# Codec_main.net
KiCad netlist of a schematic drawn in EAGLE
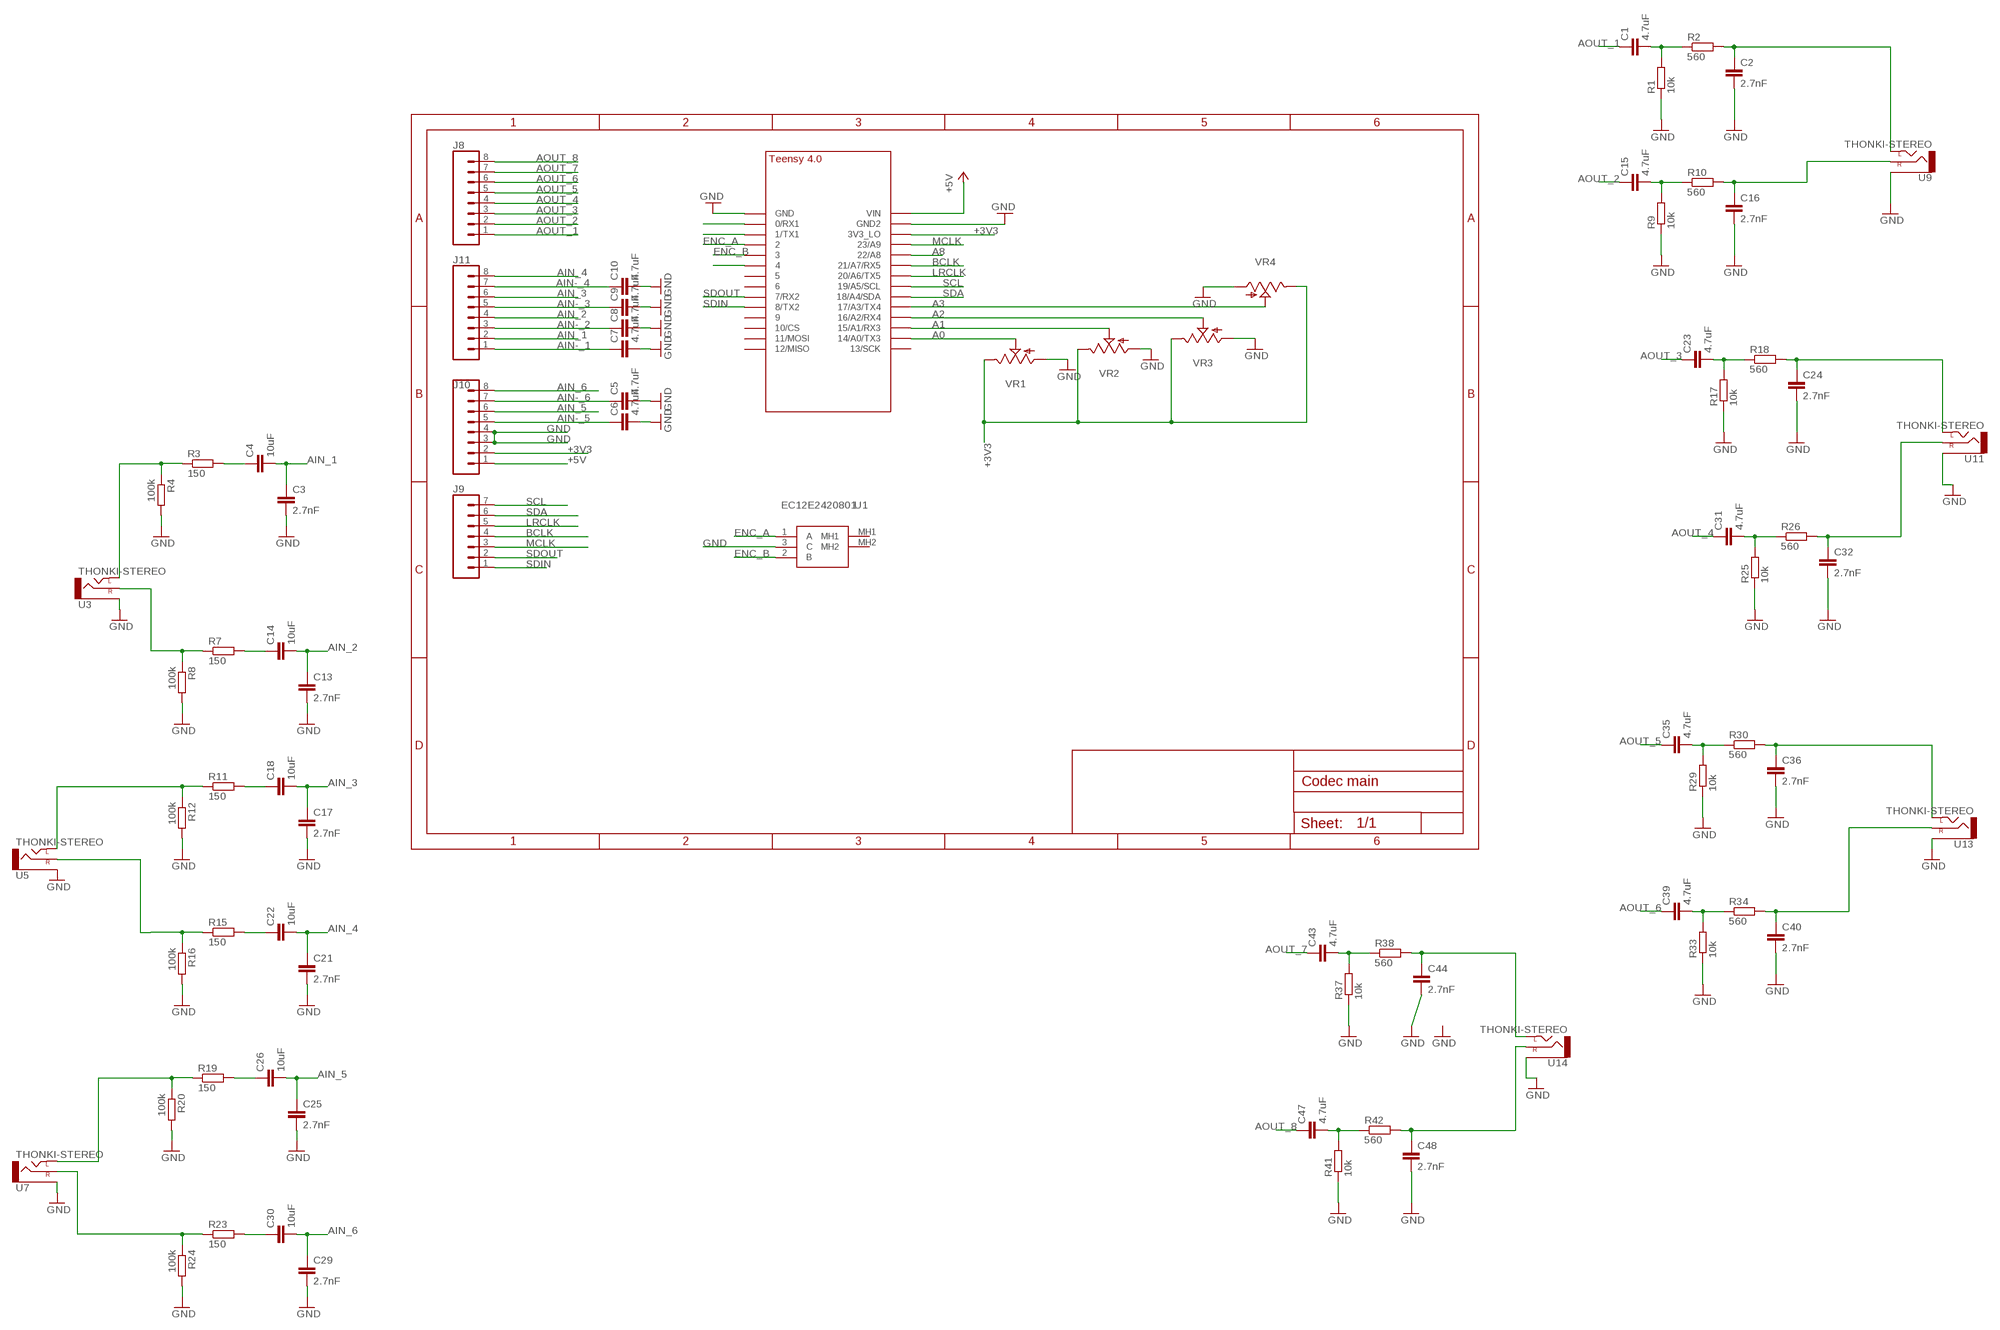
[diagram p0: schematic, sheet 1]

(export (version "E")
  (design (tool "Eeschema 10.0.6"))
  (components
    (comp (ref "C1")
      (value "4.7uF")
      (footprint "eagle-import:C0805")
      (libsource (lib "eagle-import") (part "C-EUC0805"))
    )
    (comp (ref "C2")
      (value "2.7nF")
      (footprint "eagle-import:C0805")
      (libsource (lib "eagle-import") (part "C-EUC0805"))
    )
    (comp (ref "C3")
      (value "2.7nF")
      (footprint "eagle-import:C0805")
      (libsource (lib "eagle-import") (part "C-EUC0805"))
    )
    (comp (ref "C4")
      (value "10uF")
      (footprint "eagle-import:C0805")
      (libsource (lib "eagle-import") (part "C-EUC0805"))
    )
    (comp (ref "C5")
      (value "4.7uF")
      (footprint "eagle-import:C0805")
      (libsource (lib "eagle-import") (part "C-EUC0805"))
    )
    (comp (ref "C6")
      (value "4.7uF")
      (footprint "eagle-import:C0805")
      (libsource (lib "eagle-import") (part "C-EUC0805"))
    )
    (comp (ref "C7")
      (value "4.7uF")
      (footprint "eagle-import:C0805")
      (libsource (lib "eagle-import") (part "C-EUC0805"))
    )
    (comp (ref "C8")
      (value "4.7uF")
      (footprint "eagle-import:C0805")
      (libsource (lib "eagle-import") (part "C-EUC0805"))
    )
    (comp (ref "C9")
      (value "4.7uF")
      (footprint "eagle-import:C0805")
      (libsource (lib "eagle-import") (part "C-EUC0805"))
    )
    (comp (ref "C10")
      (value "4.7uF")
      (footprint "eagle-import:C0805")
      (libsource (lib "eagle-import") (part "C-EUC0805"))
    )
    (comp (ref "C13")
      (value "2.7nF")
      (footprint "eagle-import:C0805")
      (libsource (lib "eagle-import") (part "C-EUC0805"))
    )
    (comp (ref "C14")
      (value "10uF")
      (footprint "eagle-import:C0805")
      (libsource (lib "eagle-import") (part "C-EUC0805"))
    )
    (comp (ref "C15")
      (value "4.7uF")
      (footprint "eagle-import:C0805")
      (libsource (lib "eagle-import") (part "C-EUC0805"))
    )
    (comp (ref "C16")
      (value "2.7nF")
      (footprint "eagle-import:C0805")
      (libsource (lib "eagle-import") (part "C-EUC0805"))
    )
    (comp (ref "C17")
      (value "2.7nF")
      (footprint "eagle-import:C0805")
      (libsource (lib "eagle-import") (part "C-EUC0805"))
    )
    (comp (ref "C18")
      (value "10uF")
      (footprint "eagle-import:C0805")
      (libsource (lib "eagle-import") (part "C-EUC0805"))
    )
    (comp (ref "C21")
      (value "2.7nF")
      (footprint "eagle-import:C0805")
      (libsource (lib "eagle-import") (part "C-EUC0805"))
    )
    (comp (ref "C22")
      (value "10uF")
      (footprint "eagle-import:C0805")
      (libsource (lib "eagle-import") (part "C-EUC0805"))
    )
    (comp (ref "C23")
      (value "4.7uF")
      (footprint "eagle-import:C0805")
      (libsource (lib "eagle-import") (part "C-EUC0805"))
    )
    (comp (ref "C24")
      (value "2.7nF")
      (footprint "eagle-import:C0805")
      (libsource (lib "eagle-import") (part "C-EUC0805"))
    )
    (comp (ref "C25")
      (value "2.7nF")
      (footprint "eagle-import:C0805")
      (libsource (lib "eagle-import") (part "C-EUC0805"))
    )
    (comp (ref "C26")
      (value "10uF")
      (footprint "eagle-import:C0805")
      (libsource (lib "eagle-import") (part "C-EUC0805"))
    )
    (comp (ref "C29")
      (value "2.7nF")
      (footprint "eagle-import:C0805")
      (libsource (lib "eagle-import") (part "C-EUC0805"))
    )
    (comp (ref "C30")
      (value "10uF")
      (footprint "eagle-import:C0805")
      (libsource (lib "eagle-import") (part "C-EUC0805"))
    )
    (comp (ref "C31")
      (value "4.7uF")
      (footprint "eagle-import:C0805")
      (libsource (lib "eagle-import") (part "C-EUC0805"))
    )
    (comp (ref "C32")
      (value "2.7nF")
      (footprint "eagle-import:C0805")
      (libsource (lib "eagle-import") (part "C-EUC0805"))
    )
    (comp (ref "C35")
      (value "4.7uF")
      (footprint "eagle-import:C0805")
      (libsource (lib "eagle-import") (part "C-EUC0805"))
    )
    (comp (ref "C36")
      (value "2.7nF")
      (footprint "eagle-import:C0805")
      (libsource (lib "eagle-import") (part "C-EUC0805"))
    )
    (comp (ref "C39")
      (value "4.7uF")
      (footprint "eagle-import:C0805")
      (libsource (lib "eagle-import") (part "C-EUC0805"))
    )
    (comp (ref "C40")
      (value "2.7nF")
      (footprint "eagle-import:C0805")
      (libsource (lib "eagle-import") (part "C-EUC0805"))
    )
    (comp (ref "C43")
      (value "4.7uF")
      (footprint "eagle-import:C0805")
      (libsource (lib "eagle-import") (part "C-EUC0805"))
    )
    (comp (ref "C44")
      (value "2.7nF")
      (footprint "eagle-import:C0805")
      (libsource (lib "eagle-import") (part "C-EUC0805"))
    )
    (comp (ref "C47")
      (value "4.7uF")
      (footprint "eagle-import:C0805")
      (libsource (lib "eagle-import") (part "C-EUC0805"))
    )
    (comp (ref "C48")
      (value "2.7nF")
      (footprint "eagle-import:C0805")
      (libsource (lib "eagle-import") (part "C-EUC0805"))
    )
    (comp (ref "J8")
      (value "CONN_08\"")
      (footprint "eagle-import:1X08")
      (libsource (lib "eagle-import") (part "CONN_08{dblquote}"))
    )
    (comp (ref "J9")
      (value "CONN_07")
      (footprint "eagle-import:1X07")
      (libsource (lib "eagle-import") (part "CONN_07"))
    )
    (comp (ref "J10")
      (value "CONN_08\"")
      (footprint "eagle-import:1X08")
      (libsource (lib "eagle-import") (part "CONN_08{dblquote}"))
    )
    (comp (ref "J11")
      (value "CONN_08\"")
      (footprint "eagle-import:1X08")
      (libsource (lib "eagle-import") (part "CONN_08{dblquote}"))
    )
    (comp (ref "R1")
      (value "10k")
      (footprint "eagle-import:R0603")
      (libsource (lib "eagle-import") (part "R-EU_R0603"))
    )
    (comp (ref "R2")
      (value "560")
      (footprint "eagle-import:M0805")
      (libsource (lib "eagle-import") (part "R-EU_M0805"))
    )
    (comp (ref "R3")
      (value "150")
      (footprint "eagle-import:M0805")
      (libsource (lib "eagle-import") (part "R-EU_M0805"))
    )
    (comp (ref "R4")
      (value "100k")
      (footprint "eagle-import:R0603")
      (libsource (lib "eagle-import") (part "R-EU_R0603"))
    )
    (comp (ref "R7")
      (value "150")
      (footprint "eagle-import:M0805")
      (libsource (lib "eagle-import") (part "R-EU_M0805"))
    )
    (comp (ref "R8")
      (value "100k")
      (footprint "eagle-import:R0603")
      (libsource (lib "eagle-import") (part "R-EU_R0603"))
    )
    (comp (ref "R9")
      (value "10k")
      (footprint "eagle-import:R0603")
      (libsource (lib "eagle-import") (part "R-EU_R0603"))
    )
    (comp (ref "R10")
      (value "560")
      (footprint "eagle-import:M0805")
      (libsource (lib "eagle-import") (part "R-EU_M0805"))
    )
    (comp (ref "R11")
      (value "150")
      (footprint "eagle-import:M0805")
      (libsource (lib "eagle-import") (part "R-EU_M0805"))
    )
    (comp (ref "R12")
      (value "100k")
      (footprint "eagle-import:R0603")
      (libsource (lib "eagle-import") (part "R-EU_R0603"))
    )
    (comp (ref "R15")
      (value "150")
      (footprint "eagle-import:M0805")
      (libsource (lib "eagle-import") (part "R-EU_M0805"))
    )
    (comp (ref "R16")
      (value "100k")
      (footprint "eagle-import:R0603")
      (libsource (lib "eagle-import") (part "R-EU_R0603"))
    )
    (comp (ref "R17")
      (value "10k")
      (footprint "eagle-import:R0603")
      (libsource (lib "eagle-import") (part "R-EU_R0603"))
    )
    (comp (ref "R18")
      (value "560")
      (footprint "eagle-import:M0805")
      (libsource (lib "eagle-import") (part "R-EU_M0805"))
    )
    (comp (ref "R19")
      (value "150")
      (footprint "eagle-import:M0805")
      (libsource (lib "eagle-import") (part "R-EU_M0805"))
    )
    (comp (ref "R20")
      (value "100k")
      (footprint "eagle-import:R0603")
      (libsource (lib "eagle-import") (part "R-EU_R0603"))
    )
    (comp (ref "R23")
      (value "150")
      (footprint "eagle-import:M0805")
      (libsource (lib "eagle-import") (part "R-EU_M0805"))
    )
    (comp (ref "R24")
      (value "100k")
      (footprint "eagle-import:R0603")
      (libsource (lib "eagle-import") (part "R-EU_R0603"))
    )
    (comp (ref "R25")
      (value "10k")
      (footprint "eagle-import:R0603")
      (libsource (lib "eagle-import") (part "R-EU_R0603"))
    )
    (comp (ref "R26")
      (value "560")
      (footprint "eagle-import:M0805")
      (libsource (lib "eagle-import") (part "R-EU_M0805"))
    )
    (comp (ref "R29")
      (value "10k")
      (footprint "eagle-import:R0603")
      (libsource (lib "eagle-import") (part "R-EU_R0603"))
    )
    (comp (ref "R30")
      (value "560")
      (footprint "eagle-import:M0805")
      (libsource (lib "eagle-import") (part "R-EU_M0805"))
    )
    (comp (ref "R33")
      (value "10k")
      (footprint "eagle-import:R0603")
      (libsource (lib "eagle-import") (part "R-EU_R0603"))
    )
    (comp (ref "R34")
      (value "560")
      (footprint "eagle-import:M0805")
      (libsource (lib "eagle-import") (part "R-EU_M0805"))
    )
    (comp (ref "R37")
      (value "10k")
      (footprint "eagle-import:R0603")
      (libsource (lib "eagle-import") (part "R-EU_R0603"))
    )
    (comp (ref "R38")
      (value "560")
      (footprint "eagle-import:M0805")
      (libsource (lib "eagle-import") (part "R-EU_M0805"))
    )
    (comp (ref "R41")
      (value "10k")
      (footprint "eagle-import:R0603")
      (libsource (lib "eagle-import") (part "R-EU_R0603"))
    )
    (comp (ref "R42")
      (value "560")
      (footprint "eagle-import:M0805")
      (libsource (lib "eagle-import") (part "R-EU_M0805"))
    )
    (comp (ref "U$1")
      (value "TEENSY_4.0")
      (footprint "eagle-import:TEENSY_4.0")
      (libsource (lib "eagle-import") (part "TEENSY_4.0"))
    )
    (comp (ref "U1")
      (value "EC12E2420801")
      (footprint "eagle-import:EC12E2420801")
      (fields (field (name "MOUSER_PART_NUMBER") "688-EC12E2420801"))
      (libsource (lib "eagle-import") (part "EC12E2420801"))
    )
    (comp (ref "U3")
      (value "THONKI-STEREO")
      (footprint "eagle-import:WQP-PJ366ST_JACK")
      (libsource (lib "eagle-import") (part "THONKI-STEREO"))
    )
    (comp (ref "U5")
      (value "THONKI-STEREO")
      (footprint "eagle-import:WQP-PJ366ST_JACK")
      (libsource (lib "eagle-import") (part "THONKI-STEREO"))
    )
    (comp (ref "U7")
      (value "THONKI-STEREO")
      (footprint "eagle-import:WQP-PJ366ST_JACK")
      (libsource (lib "eagle-import") (part "THONKI-STEREO"))
    )
    (comp (ref "U9")
      (value "THONKI-STEREO")
      (footprint "eagle-import:WQP-PJ366ST_JACK")
      (libsource (lib "eagle-import") (part "THONKI-STEREO"))
    )
    (comp (ref "U11")
      (value "THONKI-STEREO")
      (footprint "eagle-import:WQP-PJ366ST_JACK")
      (libsource (lib "eagle-import") (part "THONKI-STEREO"))
    )
    (comp (ref "U13")
      (value "THONKI-STEREO")
      (footprint "eagle-import:WQP-PJ366ST_JACK")
      (libsource (lib "eagle-import") (part "THONKI-STEREO"))
    )
    (comp (ref "U14")
      (value "THONKI-STEREO")
      (footprint "eagle-import:WQP-PJ366ST_JACK")
      (libsource (lib "eagle-import") (part "THONKI-STEREO"))
    )
    (comp (ref "VR1")
      (value "9MM_SNAP-IN_POT_")
      (footprint "eagle-import:9MM_SNAP-IN_POT")
      (libsource (lib "eagle-import") (part "9MM_SNAP-IN_POT_"))
    )
    (comp (ref "VR2")
      (value "9MM_SNAP-IN_POT_")
      (footprint "eagle-import:9MM_SNAP-IN_POT")
      (libsource (lib "eagle-import") (part "9MM_SNAP-IN_POT_"))
    )
    (comp (ref "VR3")
      (value "9MM_SNAP-IN_POT_")
      (footprint "eagle-import:9MM_SNAP-IN_POT")
      (libsource (lib "eagle-import") (part "9MM_SNAP-IN_POT_"))
    )
    (comp (ref "VR4")
      (value "9MM_SNAP-IN_POT_")
      (footprint "eagle-import:9MM_SNAP-IN_POT")
      (libsource (lib "eagle-import") (part "9MM_SNAP-IN_POT_"))
    )
  )
  (nets
    (net (code "1") (name "+5V") (class "Default")
      (node (ref "J10") (pin "1") (pinfunction "1_1") (pintype "passive"))
      (node (ref "U$1") (pin "VIN") (pinfunction "VIN_VIN") (pintype "bidirectional"))
    )
    (net (code "2") (name "/+3V3") (class "Default")
      (node (ref "J10") (pin "2") (pinfunction "2_2") (pintype "passive"))
      (node (ref "U$1") (pin "3V3_LO") (pinfunction "3V3_LO_3V3_LO") (pintype "bidirectional"))
      (node (ref "VR1") (pin "3") (pinfunction "E_3") (pintype "passive"))
      (node (ref "VR2") (pin "3") (pinfunction "E_3") (pintype "passive"))
      (node (ref "VR3") (pin "3") (pinfunction "E_3") (pintype "passive"))
      (node (ref "VR4") (pin "3") (pinfunction "E_3") (pintype "passive"))
    )
    (net (code "3") (name "/A0") (class "Default")
      (node (ref "U$1") (pin "14/A0") (pinfunction "14/A0/TX3_14/A0") (pintype "bidirectional"))
      (node (ref "VR1") (pin "2") (pinfunction "S_2") (pintype "passive"))
    )
    (net (code "4") (name "/A1") (class "Default")
      (node (ref "U$1") (pin "15/A1") (pinfunction "15/A1/RX3_15/A1") (pintype "bidirectional"))
      (node (ref "VR2") (pin "2") (pinfunction "S_2") (pintype "passive"))
    )
    (net (code "5") (name "/A2") (class "Default")
      (node (ref "U$1") (pin "16/A2") (pinfunction "16/A2/RX4_16/A2") (pintype "bidirectional"))
      (node (ref "VR3") (pin "2") (pinfunction "S_2") (pintype "passive"))
    )
    (net (code "6") (name "/A3") (class "Default")
      (node (ref "U$1") (pin "17/A3") (pinfunction "17/A3/TX4_17/A3") (pintype "bidirectional"))
      (node (ref "VR4") (pin "2") (pinfunction "S_2") (pintype "passive"))
    )
    (net (code "7") (name "/A8") (class "Default")
      (node (ref "U$1") (pin "22/A8") (pinfunction "22/A8_22/A8") (pintype "bidirectional"))
    )
    (net (code "8") (name "/AIN-_1") (class "Default")
      (node (ref "C7") (pin "1") (pinfunction "1_1") (pintype "passive"))
      (node (ref "J11") (pin "1") (pinfunction "1_1") (pintype "passive"))
    )
    (net (code "9") (name "/AIN-_2") (class "Default")
      (node (ref "C8") (pin "1") (pinfunction "1_1") (pintype "passive"))
      (node (ref "J11") (pin "3") (pinfunction "3_3") (pintype "passive"))
    )
    (net (code "10") (name "/AIN-_3") (class "Default")
      (node (ref "C9") (pin "1") (pinfunction "1_1") (pintype "passive"))
      (node (ref "J11") (pin "5") (pinfunction "5_5") (pintype "passive"))
    )
    (net (code "11") (name "/AIN-_4") (class "Default")
      (node (ref "C10") (pin "1") (pinfunction "1_1") (pintype "passive"))
      (node (ref "J11") (pin "7") (pinfunction "7_7") (pintype "passive"))
    )
    (net (code "12") (name "/AIN-_5") (class "Default")
      (node (ref "C6") (pin "1") (pinfunction "1_1") (pintype "passive"))
      (node (ref "J10") (pin "5") (pinfunction "5_5") (pintype "passive"))
    )
    (net (code "13") (name "/AIN-_6") (class "Default")
      (node (ref "C5") (pin "1") (pinfunction "1_1") (pintype "passive"))
      (node (ref "J10") (pin "7") (pinfunction "7_7") (pintype "passive"))
    )
    (net (code "14") (name "/AIN_1") (class "Default")
      (node (ref "C3") (pin "1") (pinfunction "1_1") (pintype "passive"))
      (node (ref "C4") (pin "2") (pinfunction "2_2") (pintype "passive"))
      (node (ref "J11") (pin "2") (pinfunction "2_2") (pintype "passive"))
    )
    (net (code "15") (name "/AIN_2") (class "Default")
      (node (ref "C13") (pin "1") (pinfunction "1_1") (pintype "passive"))
      (node (ref "C14") (pin "2") (pinfunction "2_2") (pintype "passive"))
      (node (ref "J11") (pin "4") (pinfunction "4_4") (pintype "passive"))
    )
    (net (code "16") (name "/AIN_3") (class "Default")
      (node (ref "C17") (pin "1") (pinfunction "1_1") (pintype "passive"))
      (node (ref "C18") (pin "2") (pinfunction "2_2") (pintype "passive"))
      (node (ref "J11") (pin "6") (pinfunction "6_6") (pintype "passive"))
    )
    (net (code "17") (name "/AIN_4") (class "Default")
      (node (ref "C21") (pin "1") (pinfunction "1_1") (pintype "passive"))
      (node (ref "C22") (pin "2") (pinfunction "2_2") (pintype "passive"))
      (node (ref "J11") (pin "8") (pinfunction "8_8") (pintype "passive"))
    )
    (net (code "18") (name "/AIN_5") (class "Default")
      (node (ref "C25") (pin "1") (pinfunction "1_1") (pintype "passive"))
      (node (ref "C26") (pin "2") (pinfunction "2_2") (pintype "passive"))
      (node (ref "J10") (pin "6") (pinfunction "6_6") (pintype "passive"))
    )
    (net (code "19") (name "/AIN_6") (class "Default")
      (node (ref "C29") (pin "1") (pinfunction "1_1") (pintype "passive"))
      (node (ref "C30") (pin "2") (pinfunction "2_2") (pintype "passive"))
      (node (ref "J10") (pin "8") (pinfunction "8_8") (pintype "passive"))
    )
    (net (code "20") (name "/AOUT_1") (class "Default")
      (node (ref "C1") (pin "1") (pinfunction "1_1") (pintype "passive"))
      (node (ref "J8") (pin "1") (pinfunction "1_1") (pintype "passive"))
    )
    (net (code "21") (name "/AOUT_2") (class "Default")
      (node (ref "C15") (pin "1") (pinfunction "1_1") (pintype "passive"))
      (node (ref "J8") (pin "2") (pinfunction "2_2") (pintype "passive"))
    )
    (net (code "22") (name "/AOUT_3") (class "Default")
      (node (ref "C23") (pin "1") (pinfunction "1_1") (pintype "passive"))
      (node (ref "J8") (pin "3") (pinfunction "3_3") (pintype "passive"))
    )
    (net (code "23") (name "/AOUT_4") (class "Default")
      (node (ref "C31") (pin "1") (pinfunction "1_1") (pintype "passive"))
      (node (ref "J8") (pin "4") (pinfunction "4_4") (pintype "passive"))
    )
    (net (code "24") (name "/AOUT_5") (class "Default")
      (node (ref "C35") (pin "1") (pinfunction "1_1") (pintype "passive"))
      (node (ref "J8") (pin "5") (pinfunction "5_5") (pintype "passive"))
    )
    (net (code "25") (name "/AOUT_6") (class "Default")
      (node (ref "C39") (pin "1") (pinfunction "1_1") (pintype "passive"))
      (node (ref "J8") (pin "6") (pinfunction "6_6") (pintype "passive"))
    )
    (net (code "26") (name "/AOUT_7") (class "Default")
      (node (ref "C43") (pin "1") (pinfunction "1_1") (pintype "passive"))
      (node (ref "J8") (pin "7") (pinfunction "7_7") (pintype "passive"))
    )
    (net (code "27") (name "/AOUT_8") (class "Default")
      (node (ref "C47") (pin "1") (pinfunction "1_1") (pintype "passive"))
      (node (ref "J8") (pin "8") (pinfunction "8_8") (pintype "passive"))
    )
    (net (code "28") (name "/BCLK") (class "Default")
      (node (ref "J9") (pin "4") (pinfunction "4_4") (pintype "passive"))
      (node (ref "U$1") (pin "21/A7") (pinfunction "21/A7/RX5_21/A7") (pintype "bidirectional"))
    )
    (net (code "29") (name "/ENC_A") (class "Default")
      (node (ref "U$1") (pin "2") (pinfunction "2_2") (pintype "bidirectional"))
      (node (ref "U1") (pin "1") (pinfunction "A_1") (pintype "bidirectional"))
    )
    (net (code "30") (name "/ENC_B") (class "Default")
      (node (ref "U$1") (pin "3/CANTX") (pinfunction "3_3/CANTX") (pintype "bidirectional"))
      (node (ref "U1") (pin "2") (pinfunction "B_2") (pintype "bidirectional"))
    )
    (net (code "31") (name "/LRCLK") (class "Default")
      (node (ref "J9") (pin "5") (pinfunction "5_5") (pintype "passive"))
      (node (ref "U$1") (pin "20/A6") (pinfunction "20/A6/TX5_20/A6") (pintype "bidirectional"))
    )
    (net (code "32") (name "/MCLK") (class "Default")
      (node (ref "J9") (pin "3") (pinfunction "3_3") (pintype "passive"))
      (node (ref "U$1") (pin "23/A9") (pinfunction "23/A9_23/A9") (pintype "bidirectional"))
    )
    (net (code "33") (name "/SCL") (class "Default")
      (node (ref "J9") (pin "7") (pinfunction "7_7") (pintype "passive"))
      (node (ref "U$1") (pin "19/A5/SCL") (pinfunction "19/A5/SCL_19/A5/SCL") (pintype "bidirectional"))
    )
    (net (code "34") (name "/SDA") (class "Default")
      (node (ref "J9") (pin "6") (pinfunction "6_6") (pintype "passive"))
      (node (ref "U$1") (pin "18/A4/SDA") (pinfunction "18/A4/SDA_18/A4/SDA") (pintype "bidirectional"))
    )
    (net (code "35") (name "/SDIN") (class "Default")
      (node (ref "J9") (pin "1") (pinfunction "1_1") (pintype "passive"))
      (node (ref "U$1") (pin "8") (pinfunction "8/TX2_8") (pintype "bidirectional"))
    )
    (net (code "36") (name "/SDOUT") (class "Default")
      (node (ref "J9") (pin "2") (pinfunction "2_2") (pintype "passive"))
      (node (ref "U$1") (pin "7") (pinfunction "7/RX2_7") (pintype "bidirectional"))
    )
    (net (code "37") (name "GND") (class "Default")
      (node (ref "C10") (pin "2") (pinfunction "2_2") (pintype "passive"))
      (node (ref "C13") (pin "2") (pinfunction "2_2") (pintype "passive"))
      (node (ref "C16") (pin "2") (pinfunction "2_2") (pintype "passive"))
      (node (ref "C17") (pin "2") (pinfunction "2_2") (pintype "passive"))
      (node (ref "C2") (pin "2") (pinfunction "2_2") (pintype "passive"))
      (node (ref "C21") (pin "2") (pinfunction "2_2") (pintype "passive"))
      (node (ref "C24") (pin "2") (pinfunction "2_2") (pintype "passive"))
      (node (ref "C25") (pin "2") (pinfunction "2_2") (pintype "passive"))
      (node (ref "C29") (pin "2") (pinfunction "2_2") (pintype "passive"))
      (node (ref "C3") (pin "2") (pinfunction "2_2") (pintype "passive"))
      (node (ref "C32") (pin "2") (pinfunction "2_2") (pintype "passive"))
      (node (ref "C36") (pin "2") (pinfunction "2_2") (pintype "passive"))
      (node (ref "C40") (pin "2") (pinfunction "2_2") (pintype "passive"))
      (node (ref "C44") (pin "2") (pinfunction "2_2") (pintype "passive"))
      (node (ref "C48") (pin "2") (pinfunction "2_2") (pintype "passive"))
      (node (ref "C5") (pin "2") (pinfunction "2_2") (pintype "passive"))
      (node (ref "C6") (pin "2") (pinfunction "2_2") (pintype "passive"))
      (node (ref "C7") (pin "2") (pinfunction "2_2") (pintype "passive"))
      (node (ref "C8") (pin "2") (pinfunction "2_2") (pintype "passive"))
      (node (ref "C9") (pin "2") (pinfunction "2_2") (pintype "passive"))
      (node (ref "J10") (pin "3") (pinfunction "3_3") (pintype "passive"))
      (node (ref "J10") (pin "4") (pinfunction "4_4") (pintype "passive"))
      (node (ref "R1") (pin "1") (pinfunction "1_1") (pintype "passive"))
      (node (ref "R12") (pin "2") (pinfunction "2_2") (pintype "passive"))
      (node (ref "R16") (pin "2") (pinfunction "2_2") (pintype "passive"))
      (node (ref "R17") (pin "1") (pinfunction "1_1") (pintype "passive"))
      (node (ref "R20") (pin "2") (pinfunction "2_2") (pintype "passive"))
      (node (ref "R24") (pin "2") (pinfunction "2_2") (pintype "passive"))
      (node (ref "R25") (pin "1") (pinfunction "1_1") (pintype "passive"))
      (node (ref "R29") (pin "1") (pinfunction "1_1") (pintype "passive"))
      (node (ref "R33") (pin "1") (pinfunction "1_1") (pintype "passive"))
      (node (ref "R37") (pin "1") (pinfunction "1_1") (pintype "passive"))
      (node (ref "R4") (pin "2") (pinfunction "2_2") (pintype "passive"))
      (node (ref "R41") (pin "1") (pinfunction "1_1") (pintype "passive"))
      (node (ref "R8") (pin "2") (pinfunction "2_2") (pintype "passive"))
      (node (ref "R9") (pin "1") (pinfunction "1_1") (pintype "passive"))
      (node (ref "U$1") (pin "GND") (pinfunction "GND_GND") (pintype "bidirectional"))
      (node (ref "U$1") (pin "GND2") (pinfunction "GND2_GND2") (pintype "bidirectional"))
      (node (ref "U1") (pin "3") (pinfunction "C_3") (pintype "bidirectional"))
      (node (ref "U11") (pin "P$3_SLEEVE") (pinfunction "SLEEVE_P$3_SLEEVE") (pintype "bidirectional"))
      (node (ref "U13") (pin "P$3_SLEEVE") (pinfunction "SLEEVE_P$3_SLEEVE") (pintype "bidirectional"))
      (node (ref "U14") (pin "P$3_SLEEVE") (pinfunction "SLEEVE_P$3_SLEEVE") (pintype "bidirectional"))
      (node (ref "U3") (pin "P$3_SLEEVE") (pinfunction "SLEEVE_P$3_SLEEVE") (pintype "bidirectional"))
      (node (ref "U5") (pin "P$3_SLEEVE") (pinfunction "SLEEVE_P$3_SLEEVE") (pintype "bidirectional"))
      (node (ref "U7") (pin "P$3_SLEEVE") (pinfunction "SLEEVE_P$3_SLEEVE") (pintype "bidirectional"))
      (node (ref "U9") (pin "P$3_SLEEVE") (pinfunction "SLEEVE_P$3_SLEEVE") (pintype "bidirectional"))
      (node (ref "VR1") (pin "1") (pinfunction "A_1") (pintype "passive"))
      (node (ref "VR2") (pin "1") (pinfunction "A_1") (pintype "passive"))
      (node (ref "VR3") (pin "1") (pinfunction "A_1") (pintype "passive"))
      (node (ref "VR4") (pin "1") (pinfunction "A_1") (pintype "passive"))
    )
    (net (code "38") (name "Net-(C1-Pad2)") (class "Default")
      (node (ref "C1") (pin "2") (pinfunction "2_2") (pintype "passive"))
      (node (ref "R1") (pin "2") (pinfunction "2_2") (pintype "passive"))
      (node (ref "R2") (pin "1") (pinfunction "1_1") (pintype "passive"))
    )
    (net (code "39") (name "Net-(C4-Pad1)") (class "Default")
      (node (ref "C4") (pin "1") (pinfunction "1_1") (pintype "passive"))
      (node (ref "R3") (pin "2") (pinfunction "2_2") (pintype "passive"))
    )
    (net (code "40") (name "Net-(C14-Pad1)") (class "Default")
      (node (ref "C14") (pin "1") (pinfunction "1_1") (pintype "passive"))
      (node (ref "R7") (pin "2") (pinfunction "2_2") (pintype "passive"))
    )
    (net (code "41") (name "Net-(C15-Pad2)") (class "Default")
      (node (ref "C15") (pin "2") (pinfunction "2_2") (pintype "passive"))
      (node (ref "R10") (pin "1") (pinfunction "1_1") (pintype "passive"))
      (node (ref "R9") (pin "2") (pinfunction "2_2") (pintype "passive"))
    )
    (net (code "42") (name "Net-(C18-Pad1)") (class "Default")
      (node (ref "C18") (pin "1") (pinfunction "1_1") (pintype "passive"))
      (node (ref "R11") (pin "2") (pinfunction "2_2") (pintype "passive"))
    )
    (net (code "43") (name "Net-(C22-Pad1)") (class "Default")
      (node (ref "C22") (pin "1") (pinfunction "1_1") (pintype "passive"))
      (node (ref "R15") (pin "2") (pinfunction "2_2") (pintype "passive"))
    )
    (net (code "44") (name "Net-(C23-Pad2)") (class "Default")
      (node (ref "C23") (pin "2") (pinfunction "2_2") (pintype "passive"))
      (node (ref "R17") (pin "2") (pinfunction "2_2") (pintype "passive"))
      (node (ref "R18") (pin "1") (pinfunction "1_1") (pintype "passive"))
    )
    (net (code "45") (name "Net-(C26-Pad1)") (class "Default")
      (node (ref "C26") (pin "1") (pinfunction "1_1") (pintype "passive"))
      (node (ref "R19") (pin "2") (pinfunction "2_2") (pintype "passive"))
    )
    (net (code "46") (name "Net-(C30-Pad1)") (class "Default")
      (node (ref "C30") (pin "1") (pinfunction "1_1") (pintype "passive"))
      (node (ref "R23") (pin "2") (pinfunction "2_2") (pintype "passive"))
    )
    (net (code "47") (name "Net-(C31-Pad2)") (class "Default")
      (node (ref "C31") (pin "2") (pinfunction "2_2") (pintype "passive"))
      (node (ref "R25") (pin "2") (pinfunction "2_2") (pintype "passive"))
      (node (ref "R26") (pin "1") (pinfunction "1_1") (pintype "passive"))
    )
    (net (code "48") (name "Net-(C35-Pad2)") (class "Default")
      (node (ref "C35") (pin "2") (pinfunction "2_2") (pintype "passive"))
      (node (ref "R29") (pin "2") (pinfunction "2_2") (pintype "passive"))
      (node (ref "R30") (pin "1") (pinfunction "1_1") (pintype "passive"))
    )
    (net (code "49") (name "Net-(C39-Pad2)") (class "Default")
      (node (ref "C39") (pin "2") (pinfunction "2_2") (pintype "passive"))
      (node (ref "R33") (pin "2") (pinfunction "2_2") (pintype "passive"))
      (node (ref "R34") (pin "1") (pinfunction "1_1") (pintype "passive"))
    )
    (net (code "50") (name "Net-(C43-Pad2)") (class "Default")
      (node (ref "C43") (pin "2") (pinfunction "2_2") (pintype "passive"))
      (node (ref "R37") (pin "2") (pinfunction "2_2") (pintype "passive"))
      (node (ref "R38") (pin "1") (pinfunction "1_1") (pintype "passive"))
    )
    (net (code "51") (name "Net-(C47-Pad2)") (class "Default")
      (node (ref "C47") (pin "2") (pinfunction "2_2") (pintype "passive"))
      (node (ref "R41") (pin "2") (pinfunction "2_2") (pintype "passive"))
      (node (ref "R42") (pin "1") (pinfunction "1_1") (pintype "passive"))
    )
    (net (code "52") (name "Net-(U3-LEFT)") (class "Default")
      (node (ref "R3") (pin "1") (pinfunction "1_1") (pintype "passive"))
      (node (ref "R4") (pin "1") (pinfunction "1_1") (pintype "passive"))
      (node (ref "U3") (pin "P$1_TIP") (pinfunction "LEFT_P$1_TIP") (pintype "bidirectional"))
    )
    (net (code "53") (name "Net-(U3-RIGHT)") (class "Default")
      (node (ref "R7") (pin "1") (pinfunction "1_1") (pintype "passive"))
      (node (ref "R8") (pin "1") (pinfunction "1_1") (pintype "passive"))
      (node (ref "U3") (pin "P$2_SWITCH") (pinfunction "RIGHT_P$2_SWITCH") (pintype "bidirectional"))
    )
    (net (code "54") (name "Net-(U5-LEFT)") (class "Default")
      (node (ref "R11") (pin "1") (pinfunction "1_1") (pintype "passive"))
      (node (ref "R12") (pin "1") (pinfunction "1_1") (pintype "passive"))
      (node (ref "U5") (pin "P$1_TIP") (pinfunction "LEFT_P$1_TIP") (pintype "bidirectional"))
    )
    (net (code "55") (name "Net-(U5-RIGHT)") (class "Default")
      (node (ref "R15") (pin "1") (pinfunction "1_1") (pintype "passive"))
      (node (ref "R16") (pin "1") (pinfunction "1_1") (pintype "passive"))
      (node (ref "U5") (pin "P$2_SWITCH") (pinfunction "RIGHT_P$2_SWITCH") (pintype "bidirectional"))
    )
    (net (code "56") (name "Net-(U7-LEFT)") (class "Default")
      (node (ref "R19") (pin "1") (pinfunction "1_1") (pintype "passive"))
      (node (ref "R20") (pin "1") (pinfunction "1_1") (pintype "passive"))
      (node (ref "U7") (pin "P$1_TIP") (pinfunction "LEFT_P$1_TIP") (pintype "bidirectional"))
    )
    (net (code "57") (name "Net-(U7-RIGHT)") (class "Default")
      (node (ref "R23") (pin "1") (pinfunction "1_1") (pintype "passive"))
      (node (ref "R24") (pin "1") (pinfunction "1_1") (pintype "passive"))
      (node (ref "U7") (pin "P$2_SWITCH") (pinfunction "RIGHT_P$2_SWITCH") (pintype "bidirectional"))
    )
    (net (code "58") (name "Net-(U9-LEFT)") (class "Default")
      (node (ref "C2") (pin "1") (pinfunction "1_1") (pintype "passive"))
      (node (ref "R2") (pin "2") (pinfunction "2_2") (pintype "passive"))
      (node (ref "U9") (pin "P$1_TIP") (pinfunction "LEFT_P$1_TIP") (pintype "bidirectional"))
    )
    (net (code "59") (name "Net-(U9-RIGHT)") (class "Default")
      (node (ref "C16") (pin "1") (pinfunction "1_1") (pintype "passive"))
      (node (ref "R10") (pin "2") (pinfunction "2_2") (pintype "passive"))
      (node (ref "U9") (pin "P$2_SWITCH") (pinfunction "RIGHT_P$2_SWITCH") (pintype "bidirectional"))
    )
    (net (code "60") (name "Net-(U11-LEFT)") (class "Default")
      (node (ref "C24") (pin "1") (pinfunction "1_1") (pintype "passive"))
      (node (ref "R18") (pin "2") (pinfunction "2_2") (pintype "passive"))
      (node (ref "U11") (pin "P$1_TIP") (pinfunction "LEFT_P$1_TIP") (pintype "bidirectional"))
    )
    (net (code "61") (name "Net-(U11-RIGHT)") (class "Default")
      (node (ref "C32") (pin "1") (pinfunction "1_1") (pintype "passive"))
      (node (ref "R26") (pin "2") (pinfunction "2_2") (pintype "passive"))
      (node (ref "U11") (pin "P$2_SWITCH") (pinfunction "RIGHT_P$2_SWITCH") (pintype "bidirectional"))
    )
    (net (code "62") (name "Net-(U13-LEFT)") (class "Default")
      (node (ref "C36") (pin "1") (pinfunction "1_1") (pintype "passive"))
      (node (ref "R30") (pin "2") (pinfunction "2_2") (pintype "passive"))
      (node (ref "U13") (pin "P$1_TIP") (pinfunction "LEFT_P$1_TIP") (pintype "bidirectional"))
    )
    (net (code "63") (name "Net-(U13-RIGHT)") (class "Default")
      (node (ref "C40") (pin "1") (pinfunction "1_1") (pintype "passive"))
      (node (ref "R34") (pin "2") (pinfunction "2_2") (pintype "passive"))
      (node (ref "U13") (pin "P$2_SWITCH") (pinfunction "RIGHT_P$2_SWITCH") (pintype "bidirectional"))
    )
    (net (code "64") (name "Net-(U14-LEFT)") (class "Default")
      (node (ref "C44") (pin "1") (pinfunction "1_1") (pintype "passive"))
      (node (ref "R38") (pin "2") (pinfunction "2_2") (pintype "passive"))
      (node (ref "U14") (pin "P$1_TIP") (pinfunction "LEFT_P$1_TIP") (pintype "bidirectional"))
    )
    (net (code "65") (name "Net-(U14-RIGHT)") (class "Default")
      (node (ref "C48") (pin "1") (pinfunction "1_1") (pintype "passive"))
      (node (ref "R42") (pin "2") (pinfunction "2_2") (pintype "passive"))
      (node (ref "U14") (pin "P$2_SWITCH") (pinfunction "RIGHT_P$2_SWITCH") (pintype "bidirectional"))
    )
    (net (code "66") (name "unconnected-(U$1-0{slash}RX1-Pad0{slash}RX)") (class "Default")
      (node (ref "U$1") (pin "0/RX") (pinfunction "0/RX1_0/RX") (pintype "bidirectional"))
    )
    (net (code "67") (name "unconnected-(U$1-1{slash}TX1-Pad1{slash}TX)") (class "Default")
      (node (ref "U$1") (pin "1/TX") (pinfunction "1/TX1_1/TX") (pintype "bidirectional"))
    )
    (net (code "68") (name "unconnected-(U$1-4-Pad4{slash}CANRX)") (class "Default")
      (node (ref "U$1") (pin "4/CANRX") (pinfunction "4_4/CANRX") (pintype "bidirectional"))
    )
    (net (code "69") (name "unconnected-(U$1-9-Pad9{slash}CS)") (class "Default")
      (node (ref "U$1") (pin "9/CS") (pinfunction "9_9/CS") (pintype "bidirectional"))
    )
    (net (code "70") (name "unconnected-(U$1-Pad5)") (class "Default")
      (node (ref "U$1") (pin "5") (pinfunction "5_5") (pintype "bidirectional"))
    )
    (net (code "71") (name "unconnected-(U$1-Pad6)") (class "Default")
      (node (ref "U$1") (pin "6") (pinfunction "6_6") (pintype "bidirectional"))
    )
    (net (code "72") (name "unconnected-(U$1-Pad10{slash}CS)") (class "Default")
      (node (ref "U$1") (pin "10/CS") (pinfunction "10/CS_10/CS") (pintype "bidirectional"))
    )
    (net (code "73") (name "unconnected-(U$1-Pad11{slash}MOSI)") (class "Default")
      (node (ref "U$1") (pin "11/MOSI") (pinfunction "11/MOSI_11/MOSI") (pintype "bidirectional"))
    )
    (net (code "74") (name "unconnected-(U$1-Pad12{slash}MISO)") (class "Default")
      (node (ref "U$1") (pin "12/MISO") (pinfunction "12/MISO_12/MISO") (pintype "bidirectional"))
    )
    (net (code "75") (name "unconnected-(U$1-Pad13{slash}SCK)") (class "Default")
      (node (ref "U$1") (pin "13/SCK") (pinfunction "13/SCK_13/SCK") (pintype "bidirectional"))
    )
    (net (code "76") (name "unconnected-(U1-PadMH1)") (class "Default")
      (node (ref "U1") (pin "MH1") (pinfunction "MH1_MH1") (pintype "bidirectional"))
    )
    (net (code "77") (name "unconnected-(U1-PadMH2)") (class "Default")
      (node (ref "U1") (pin "MH2") (pinfunction "MH2_MH2") (pintype "bidirectional"))
    )
  )
)
